# Cart.net
KiCad netlist of a schematic drawn in Altium Designer
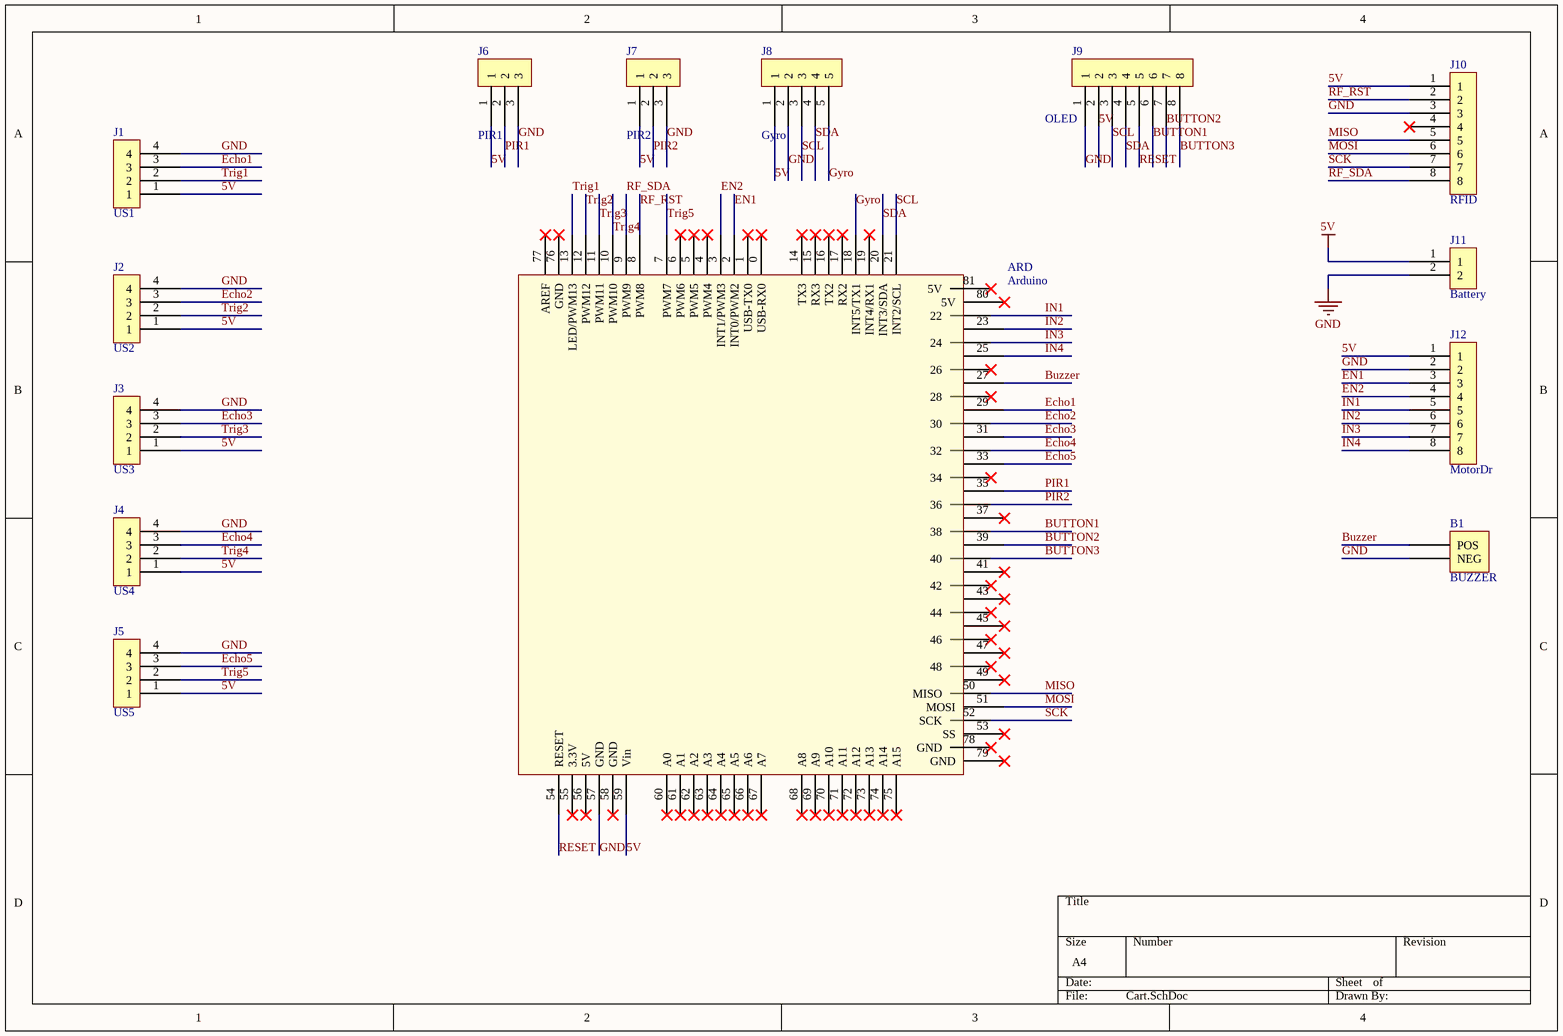
[diagram p0: Cart.SchDoc]

(export (version "E")
  (design (tool "Eeschema 10.0.6"))
  (components
    (comp (ref "ARD")
      (value "Arduino")
      (footprint "Arduino")
      (libsource (lib "Arduino System") (part "Arduino"))
    )
    (comp (ref "B1")
      (value "BUZZER")
      (footprint "new buzzer")
      (description "JST (JAPAN SOLDERLESS TERMINALS) - B8B-XH-A (LF)(SN) - HEADER, VERTICAL, 8WAY")
      (fields
        (field (name "MANUFACTURER") "JST")
        (field (name "MANUFACTURER PART NUMBER") "B8B-XH-A(LF)(SN)")
      )
      (libsource (lib "Schlib1") (part "BUZZER"))
    )
    (comp (ref "J1")
      (value "US1")
      (footprint "JST4")
      (description "JST (JAPAN SOLDERLESS TERMINALS) - B8B-XH-A (LF)(SN) - HEADER, VERTICAL, 8WAY")
      (fields
        (field (name "MANUFACTURER") "JST")
        (field (name "MANUFACTURER PART NUMBER") "B8B-XH-A(LF)(SN)")
      )
      (libsource (lib "Schlib1") (part "JST 4 PIN"))
    )
    (comp (ref "J2")
      (value "US2")
      (footprint "JST4")
      (description "JST (JAPAN SOLDERLESS TERMINALS) - B8B-XH-A (LF)(SN) - HEADER, VERTICAL, 8WAY")
      (fields
        (field (name "MANUFACTURER") "JST")
        (field (name "MANUFACTURER PART NUMBER") "B8B-XH-A(LF)(SN)")
      )
      (libsource (lib "Schlib1") (part "JST 4 PIN"))
    )
    (comp (ref "J3")
      (value "US3")
      (footprint "JST4")
      (description "JST (JAPAN SOLDERLESS TERMINALS) - B8B-XH-A (LF)(SN) - HEADER, VERTICAL, 8WAY")
      (fields
        (field (name "MANUFACTURER") "JST")
        (field (name "MANUFACTURER PART NUMBER") "B8B-XH-A(LF)(SN)")
      )
      (libsource (lib "Schlib1") (part "JST 4 PIN"))
    )
    (comp (ref "J4")
      (value "US4")
      (footprint "JST4")
      (description "JST (JAPAN SOLDERLESS TERMINALS) - B8B-XH-A (LF)(SN) - HEADER, VERTICAL, 8WAY")
      (fields
        (field (name "MANUFACTURER") "JST")
        (field (name "MANUFACTURER PART NUMBER") "B8B-XH-A(LF)(SN)")
      )
      (libsource (lib "Schlib1") (part "JST 4 PIN"))
    )
    (comp (ref "J5")
      (value "US5")
      (footprint "JST4")
      (description "JST (JAPAN SOLDERLESS TERMINALS) - B8B-XH-A (LF)(SN) - HEADER, VERTICAL, 8WAY")
      (fields
        (field (name "MANUFACTURER") "JST")
        (field (name "MANUFACTURER PART NUMBER") "B8B-XH-A(LF)(SN)")
      )
      (libsource (lib "Schlib1") (part "JST 4 PIN"))
    )
    (comp (ref "J6")
      (value "PIR1")
      (footprint "JST3")
      (description "JST (JAPAN SOLDERLESS TERMINALS) - B8B-XH-A (LF)(SN) - HEADER, VERTICAL, 8WAY")
      (fields
        (field (name "MANUFACTURER") "JST")
        (field (name "MANUFACTURER PART NUMBER") "B8B-XH-A(LF)(SN)")
      )
      (libsource (lib "Schlib1") (part "JST 3 PIN"))
    )
    (comp (ref "J7")
      (value "PIR2")
      (footprint "JST3")
      (description "JST (JAPAN SOLDERLESS TERMINALS) - B8B-XH-A (LF)(SN) - HEADER, VERTICAL, 8WAY")
      (fields
        (field (name "MANUFACTURER") "JST")
        (field (name "MANUFACTURER PART NUMBER") "B8B-XH-A(LF)(SN)")
      )
      (libsource (lib "Schlib1") (part "JST 3 PIN"))
    )
    (comp (ref "J8")
      (value "Gyro")
      (footprint "JST5")
      (description "JST (JAPAN SOLDERLESS TERMINALS) - B8B-XH-A (LF)(SN) - HEADER, VERTICAL, 8WAY")
      (fields
        (field (name "MANUFACTURER") "JST")
        (field (name "MANUFACTURER PART NUMBER") "B8B-XH-A(LF)(SN)")
      )
      (libsource (lib "Schlib1") (part "JST 5 PIN"))
    )
    (comp (ref "J9")
      (value "OLED")
      (footprint "JST8")
      (description "JST (JAPAN SOLDERLESS TERMINALS) - B8B-XH-A (LF)(SN) - HEADER, VERTICAL, 8WAY")
      (fields
        (field (name "MANUFACTURER") "JST")
        (field (name "MANUFACTURER PART NUMBER") "B8B-XH-A(LF)(SN)")
      )
      (libsource (lib "") (part "JST 8 PIN_1"))
    )
    (comp (ref "J10")
      (value "RFID")
      (footprint "JST8")
      (description "JST (JAPAN SOLDERLESS TERMINALS) - B8B-XH-A (LF)(SN) - HEADER, VERTICAL, 8WAY")
      (fields
        (field (name "MANUFACTURER") "JST")
        (field (name "MANUFACTURER PART NUMBER") "B8B-XH-A(LF)(SN)")
      )
      (libsource (lib "Schlib1") (part "JST 8 PIN"))
    )
    (comp (ref "J11")
      (value "Battery")
      (footprint "JST2")
      (description "JST (JAPAN SOLDERLESS TERMINALS) - B8B-XH-A (LF)(SN) - HEADER, VERTICAL, 8WAY")
      (fields
        (field (name "MANUFACTURER") "JST")
        (field (name "MANUFACTURER PART NUMBER") "B8B-XH-A(LF)(SN)")
      )
      (libsource (lib "Schlib1") (part "JST 2 PIN"))
    )
    (comp (ref "J12")
      (value "MotorDr")
      (footprint "JST8")
      (description "JST (JAPAN SOLDERLESS TERMINALS) - B8B-XH-A (LF)(SN) - HEADER, VERTICAL, 8WAY")
      (fields
        (field (name "MANUFACTURER") "JST")
        (field (name "MANUFACTURER PART NUMBER") "B8B-XH-A(LF)(SN)")
      )
      (libsource (lib "Schlib1") (part "JST 8 PIN"))
    )
  )
  (nets
    (net (code "1") (name "/BUTTON1") (class "Default")
      (node (ref "ARD") (pin "38") (pinfunction "38_38") (pintype "passive"))
      (node (ref "J9") (pin "6") (pinfunction "6_6") (pintype "passive"))
    )
    (net (code "2") (name "/BUTTON2") (class "Default")
      (node (ref "ARD") (pin "39") (pinfunction "39_39") (pintype "passive"))
      (node (ref "J9") (pin "7") (pinfunction "7_7") (pintype "passive"))
    )
    (net (code "3") (name "/BUTTON3") (class "Default")
      (node (ref "ARD") (pin "40") (pinfunction "40_40") (pintype "passive"))
      (node (ref "J9") (pin "8") (pinfunction "8_8") (pintype "passive"))
    )
    (net (code "4") (name "/Buzzer") (class "Default")
      (node (ref "ARD") (pin "27") (pinfunction "27_27") (pintype "passive"))
      (node (ref "B1") (pin "1") (pinfunction "POS_1") (pintype "passive"))
    )
    (net (code "5") (name "/EN1") (class "Default")
      (node (ref "ARD") (pin "2") (pinfunction "INT0/PWM2_2") (pintype "passive"))
      (node (ref "J12") (pin "3") (pinfunction "3_3") (pintype "passive"))
    )
    (net (code "6") (name "/EN2") (class "Default")
      (node (ref "ARD") (pin "3") (pinfunction "INT1/PWM3_3") (pintype "passive"))
      (node (ref "J12") (pin "4") (pinfunction "4_4") (pintype "passive"))
    )
    (net (code "7") (name "/Echo1") (class "Default")
      (node (ref "ARD") (pin "29") (pinfunction "29_29") (pintype "passive"))
      (node (ref "J1") (pin "3") (pinfunction "3_3") (pintype "passive"))
    )
    (net (code "8") (name "/Echo2") (class "Default")
      (node (ref "ARD") (pin "30") (pinfunction "30_30") (pintype "passive"))
      (node (ref "J2") (pin "3") (pinfunction "3_3") (pintype "passive"))
    )
    (net (code "9") (name "/Echo3") (class "Default")
      (node (ref "ARD") (pin "31") (pinfunction "31_31") (pintype "passive"))
      (node (ref "J3") (pin "3") (pinfunction "3_3") (pintype "passive"))
    )
    (net (code "10") (name "/Echo4") (class "Default")
      (node (ref "ARD") (pin "32") (pinfunction "32_32") (pintype "passive"))
      (node (ref "J4") (pin "3") (pinfunction "3_3") (pintype "passive"))
    )
    (net (code "11") (name "/Echo5") (class "Default")
      (node (ref "ARD") (pin "33") (pinfunction "33_33") (pintype "passive"))
      (node (ref "J5") (pin "3") (pinfunction "3_3") (pintype "passive"))
    )
    (net (code "12") (name "/Gyro") (class "Default")
      (node (ref "ARD") (pin "18") (pinfunction "INT5/TX1_18") (pintype "passive"))
      (node (ref "J8") (pin "5") (pinfunction "5_5") (pintype "passive"))
    )
    (net (code "13") (name "/IN1") (class "Default")
      (node (ref "ARD") (pin "22") (pinfunction "22_22") (pintype "passive"))
      (node (ref "J12") (pin "5") (pinfunction "5_5") (pintype "passive"))
    )
    (net (code "14") (name "/IN2") (class "Default")
      (node (ref "ARD") (pin "23") (pinfunction "23_23") (pintype "passive"))
      (node (ref "J12") (pin "6") (pinfunction "6_6") (pintype "passive"))
    )
    (net (code "15") (name "/IN3") (class "Default")
      (node (ref "ARD") (pin "24") (pinfunction "24_24") (pintype "passive"))
      (node (ref "J12") (pin "7") (pinfunction "7_7") (pintype "passive"))
    )
    (net (code "16") (name "/IN4") (class "Default")
      (node (ref "ARD") (pin "25") (pinfunction "25_25") (pintype "passive"))
      (node (ref "J12") (pin "8") (pinfunction "8_8") (pintype "passive"))
    )
    (net (code "17") (name "/MISO") (class "Default")
      (node (ref "ARD") (pin "50") (pinfunction "MISO_50") (pintype "passive"))
      (node (ref "J10") (pin "5") (pinfunction "5_5") (pintype "passive"))
    )
    (net (code "18") (name "/MOSI") (class "Default")
      (node (ref "ARD") (pin "51") (pinfunction "MOSI_51") (pintype "passive"))
      (node (ref "J10") (pin "6") (pinfunction "6_6") (pintype "passive"))
    )
    (net (code "19") (name "/PIR1") (class "Default")
      (node (ref "ARD") (pin "35") (pinfunction "35_35") (pintype "passive"))
      (node (ref "J6") (pin "2") (pinfunction "2_2") (pintype "passive"))
    )
    (net (code "20") (name "/PIR2") (class "Default")
      (node (ref "ARD") (pin "36") (pinfunction "36_36") (pintype "passive"))
      (node (ref "J7") (pin "2") (pinfunction "2_2") (pintype "passive"))
    )
    (net (code "21") (name "/RESET") (class "Default")
      (node (ref "ARD") (pin "54") (pinfunction "RESET_54") (pintype "passive"))
      (node (ref "J9") (pin "5") (pinfunction "5_5") (pintype "passive"))
    )
    (net (code "22") (name "/RF_RST") (class "Default")
      (node (ref "ARD") (pin "8") (pinfunction "PWM8_8") (pintype "passive"))
      (node (ref "J10") (pin "2") (pinfunction "2_2") (pintype "passive"))
    )
    (net (code "23") (name "/RF_SDA") (class "Default")
      (node (ref "ARD") (pin "9") (pinfunction "PWM9_9") (pintype "passive"))
      (node (ref "J10") (pin "8") (pinfunction "8_8") (pintype "passive"))
    )
    (net (code "24") (name "/SCK") (class "Default")
      (node (ref "ARD") (pin "52") (pinfunction "SCK_52") (pintype "passive"))
      (node (ref "J10") (pin "7") (pinfunction "7_7") (pintype "passive"))
    )
    (net (code "25") (name "/SCL") (class "Default")
      (node (ref "ARD") (pin "21") (pinfunction "INT2/SCL_21") (pintype "passive"))
      (node (ref "J8") (pin "3") (pinfunction "3_3") (pintype "passive"))
      (node (ref "J9") (pin "3") (pinfunction "3_3") (pintype "passive"))
    )
    (net (code "26") (name "/SDA") (class "Default")
      (node (ref "ARD") (pin "20") (pinfunction "INT3/SDA_20") (pintype "passive"))
      (node (ref "J8") (pin "4") (pinfunction "4_4") (pintype "passive"))
      (node (ref "J9") (pin "4") (pinfunction "4_4") (pintype "passive"))
    )
    (net (code "27") (name "/Trig1") (class "Default")
      (node (ref "ARD") (pin "13") (pinfunction "LED/PWM13_13") (pintype "passive"))
      (node (ref "J1") (pin "2") (pinfunction "2_2") (pintype "passive"))
    )
    (net (code "28") (name "/Trig2") (class "Default")
      (node (ref "ARD") (pin "12") (pinfunction "PWM12_12") (pintype "passive"))
      (node (ref "J2") (pin "2") (pinfunction "2_2") (pintype "passive"))
    )
    (net (code "29") (name "/Trig3") (class "Default")
      (node (ref "ARD") (pin "11") (pinfunction "PWM11_11") (pintype "passive"))
      (node (ref "J3") (pin "2") (pinfunction "2_2") (pintype "passive"))
    )
    (net (code "30") (name "/Trig4") (class "Default")
      (node (ref "ARD") (pin "10") (pinfunction "PWM10_10") (pintype "passive"))
      (node (ref "J4") (pin "2") (pinfunction "2_2") (pintype "passive"))
    )
    (net (code "31") (name "/Trig5") (class "Default")
      (node (ref "ARD") (pin "7") (pinfunction "PWM7_7") (pintype "passive"))
      (node (ref "J5") (pin "2") (pinfunction "2_2") (pintype "passive"))
    )
    (net (code "32") (name "5V") (class "Default")
      (node (ref "ARD") (pin "59") (pinfunction "Vin_59") (pintype "passive"))
      (node (ref "J1") (pin "1") (pinfunction "1_1") (pintype "passive"))
      (node (ref "J10") (pin "1") (pinfunction "1_1") (pintype "passive"))
      (node (ref "J11") (pin "1") (pinfunction "1_1") (pintype "passive"))
      (node (ref "J12") (pin "1") (pinfunction "1_1") (pintype "passive"))
      (node (ref "J2") (pin "1") (pinfunction "1_1") (pintype "passive"))
      (node (ref "J3") (pin "1") (pinfunction "1_1") (pintype "passive"))
      (node (ref "J4") (pin "1") (pinfunction "1_1") (pintype "passive"))
      (node (ref "J5") (pin "1") (pinfunction "1_1") (pintype "passive"))
      (node (ref "J6") (pin "1") (pinfunction "1_1") (pintype "passive"))
      (node (ref "J7") (pin "1") (pinfunction "1_1") (pintype "passive"))
      (node (ref "J8") (pin "1") (pinfunction "1_1") (pintype "passive"))
      (node (ref "J9") (pin "2") (pinfunction "2_2") (pintype "passive"))
    )
    (net (code "33") (name "GND") (class "Default")
      (node (ref "ARD") (pin "57") (pinfunction "GND_57") (pintype "passive"))
      (node (ref "B1") (pin "2") (pinfunction "NEG_2") (pintype "passive"))
      (node (ref "J1") (pin "4") (pinfunction "4_4") (pintype "passive"))
      (node (ref "J10") (pin "3") (pinfunction "3_3") (pintype "passive"))
      (node (ref "J11") (pin "2") (pinfunction "2_2") (pintype "passive"))
      (node (ref "J12") (pin "2") (pinfunction "2_2") (pintype "passive"))
      (node (ref "J2") (pin "4") (pinfunction "4_4") (pintype "passive"))
      (node (ref "J3") (pin "4") (pinfunction "4_4") (pintype "passive"))
      (node (ref "J4") (pin "4") (pinfunction "4_4") (pintype "passive"))
      (node (ref "J5") (pin "4") (pinfunction "4_4") (pintype "passive"))
      (node (ref "J6") (pin "3") (pinfunction "3_3") (pintype "passive"))
      (node (ref "J7") (pin "3") (pinfunction "3_3") (pintype "passive"))
      (node (ref "J8") (pin "2") (pinfunction "2_2") (pintype "passive"))
      (node (ref "J9") (pin "1") (pinfunction "1_1") (pintype "passive"))
    )
    (net (code "34") (name "unconnected-(ARD-3.3V-Pad55)") (class "Default")
      (node (ref "ARD") (pin "55") (pinfunction "3.3V_55") (pintype "passive+no_connect"))
    )
    (net (code "35") (name "unconnected-(ARD-5V-Pad56)") (class "Default")
      (node (ref "ARD") (pin "56") (pinfunction "5V_56") (pintype "passive+no_connect"))
    )
    (net (code "36") (name "unconnected-(ARD-5V-Pad80)") (class "Default")
      (node (ref "ARD") (pin "80") (pinfunction "5V_80") (pintype "passive+no_connect"))
    )
    (net (code "37") (name "unconnected-(ARD-5V-Pad81)") (class "Default")
      (node (ref "ARD") (pin "81") (pinfunction "5V_81") (pintype "passive+no_connect"))
    )
    (net (code "38") (name "unconnected-(ARD-A0-Pad60)") (class "Default")
      (node (ref "ARD") (pin "60") (pinfunction "A0_60") (pintype "passive+no_connect"))
    )
    (net (code "39") (name "unconnected-(ARD-A1-Pad61)") (class "Default")
      (node (ref "ARD") (pin "61") (pinfunction "A1_61") (pintype "passive+no_connect"))
    )
    (net (code "40") (name "unconnected-(ARD-A2-Pad62)") (class "Default")
      (node (ref "ARD") (pin "62") (pinfunction "A2_62") (pintype "passive+no_connect"))
    )
    (net (code "41") (name "unconnected-(ARD-A3-Pad63)") (class "Default")
      (node (ref "ARD") (pin "63") (pinfunction "A3_63") (pintype "passive+no_connect"))
    )
    (net (code "42") (name "unconnected-(ARD-A4-Pad64)") (class "Default")
      (node (ref "ARD") (pin "64") (pinfunction "A4_64") (pintype "passive+no_connect"))
    )
    (net (code "43") (name "unconnected-(ARD-A5-Pad65)") (class "Default")
      (node (ref "ARD") (pin "65") (pinfunction "A5_65") (pintype "passive+no_connect"))
    )
    (net (code "44") (name "unconnected-(ARD-A6-Pad66)") (class "Default")
      (node (ref "ARD") (pin "66") (pinfunction "A6_66") (pintype "passive+no_connect"))
    )
    (net (code "45") (name "unconnected-(ARD-A7-Pad67)") (class "Default")
      (node (ref "ARD") (pin "67") (pinfunction "A7_67") (pintype "passive+no_connect"))
    )
    (net (code "46") (name "unconnected-(ARD-A8-Pad68)") (class "Default")
      (node (ref "ARD") (pin "68") (pinfunction "A8_68") (pintype "passive+no_connect"))
    )
    (net (code "47") (name "unconnected-(ARD-A9-Pad69)") (class "Default")
      (node (ref "ARD") (pin "69") (pinfunction "A9_69") (pintype "passive+no_connect"))
    )
    (net (code "48") (name "unconnected-(ARD-A10-Pad70)") (class "Default")
      (node (ref "ARD") (pin "70") (pinfunction "A10_70") (pintype "passive+no_connect"))
    )
    (net (code "49") (name "unconnected-(ARD-A11-Pad71)") (class "Default")
      (node (ref "ARD") (pin "71") (pinfunction "A11_71") (pintype "passive+no_connect"))
    )
    (net (code "50") (name "unconnected-(ARD-A12-Pad72)") (class "Default")
      (node (ref "ARD") (pin "72") (pinfunction "A12_72") (pintype "passive+no_connect"))
    )
    (net (code "51") (name "unconnected-(ARD-A13-Pad73)") (class "Default")
      (node (ref "ARD") (pin "73") (pinfunction "A13_73") (pintype "passive+no_connect"))
    )
    (net (code "52") (name "unconnected-(ARD-A14-Pad74)") (class "Default")
      (node (ref "ARD") (pin "74") (pinfunction "A14_74") (pintype "passive+no_connect"))
    )
    (net (code "53") (name "unconnected-(ARD-A15-Pad75)") (class "Default")
      (node (ref "ARD") (pin "75") (pinfunction "A15_75") (pintype "passive+no_connect"))
    )
    (net (code "54") (name "unconnected-(ARD-AREF-Pad77)") (class "Default")
      (node (ref "ARD") (pin "77") (pinfunction "AREF_77") (pintype "passive+no_connect"))
    )
    (net (code "55") (name "unconnected-(ARD-GND-Pad58)") (class "Default")
      (node (ref "ARD") (pin "58") (pinfunction "GND_58") (pintype "passive+no_connect"))
    )
    (net (code "56") (name "unconnected-(ARD-GND-Pad76)") (class "Default")
      (node (ref "ARD") (pin "76") (pinfunction "GND_76") (pintype "passive+no_connect"))
    )
    (net (code "57") (name "unconnected-(ARD-GND-Pad78)") (class "Default")
      (node (ref "ARD") (pin "78") (pinfunction "GND_78") (pintype "passive+no_connect"))
    )
    (net (code "58") (name "unconnected-(ARD-GND-Pad79)") (class "Default")
      (node (ref "ARD") (pin "79") (pinfunction "GND_79") (pintype "passive+no_connect"))
    )
    (net (code "59") (name "unconnected-(ARD-INT4{slash}RX1-Pad19)") (class "Default")
      (node (ref "ARD") (pin "19") (pinfunction "INT4/RX1_19") (pintype "passive+no_connect"))
    )
    (net (code "60") (name "unconnected-(ARD-PWM4-Pad4)") (class "Default")
      (node (ref "ARD") (pin "4") (pinfunction "PWM4_4") (pintype "passive+no_connect"))
    )
    (net (code "61") (name "unconnected-(ARD-PWM5-Pad5)") (class "Default")
      (node (ref "ARD") (pin "5") (pinfunction "PWM5_5") (pintype "passive+no_connect"))
    )
    (net (code "62") (name "unconnected-(ARD-PWM6-Pad6)") (class "Default")
      (node (ref "ARD") (pin "6") (pinfunction "PWM6_6") (pintype "passive+no_connect"))
    )
    (net (code "63") (name "unconnected-(ARD-Pad26)") (class "Default")
      (node (ref "ARD") (pin "26") (pinfunction "26_26") (pintype "passive+no_connect"))
    )
    (net (code "64") (name "unconnected-(ARD-Pad28)") (class "Default")
      (node (ref "ARD") (pin "28") (pinfunction "28_28") (pintype "passive+no_connect"))
    )
    (net (code "65") (name "unconnected-(ARD-Pad34)") (class "Default")
      (node (ref "ARD") (pin "34") (pinfunction "34_34") (pintype "passive+no_connect"))
    )
    (net (code "66") (name "unconnected-(ARD-Pad37)") (class "Default")
      (node (ref "ARD") (pin "37") (pinfunction "37_37") (pintype "passive+no_connect"))
    )
    (net (code "67") (name "unconnected-(ARD-Pad41)") (class "Default")
      (node (ref "ARD") (pin "41") (pinfunction "41_41") (pintype "passive+no_connect"))
    )
    (net (code "68") (name "unconnected-(ARD-Pad42)") (class "Default")
      (node (ref "ARD") (pin "42") (pinfunction "42_42") (pintype "passive+no_connect"))
    )
    (net (code "69") (name "unconnected-(ARD-Pad43)") (class "Default")
      (node (ref "ARD") (pin "43") (pinfunction "43_43") (pintype "passive+no_connect"))
    )
    (net (code "70") (name "unconnected-(ARD-Pad44)") (class "Default")
      (node (ref "ARD") (pin "44") (pinfunction "44_44") (pintype "passive+no_connect"))
    )
    (net (code "71") (name "unconnected-(ARD-Pad45)") (class "Default")
      (node (ref "ARD") (pin "45") (pinfunction "45_45") (pintype "passive+no_connect"))
    )
    (net (code "72") (name "unconnected-(ARD-Pad46)") (class "Default")
      (node (ref "ARD") (pin "46") (pinfunction "46_46") (pintype "passive+no_connect"))
    )
    (net (code "73") (name "unconnected-(ARD-Pad47)") (class "Default")
      (node (ref "ARD") (pin "47") (pinfunction "47_47") (pintype "passive+no_connect"))
    )
    (net (code "74") (name "unconnected-(ARD-Pad48)") (class "Default")
      (node (ref "ARD") (pin "48") (pinfunction "48_48") (pintype "passive+no_connect"))
    )
    (net (code "75") (name "unconnected-(ARD-Pad49)") (class "Default")
      (node (ref "ARD") (pin "49") (pinfunction "49_49") (pintype "passive+no_connect"))
    )
    (net (code "76") (name "unconnected-(ARD-RX2-Pad17)") (class "Default")
      (node (ref "ARD") (pin "17") (pinfunction "RX2_17") (pintype "passive+no_connect"))
    )
    (net (code "77") (name "unconnected-(ARD-RX3-Pad15)") (class "Default")
      (node (ref "ARD") (pin "15") (pinfunction "RX3_15") (pintype "passive+no_connect"))
    )
    (net (code "78") (name "unconnected-(ARD-SS-Pad53)") (class "Default")
      (node (ref "ARD") (pin "53") (pinfunction "SS_53") (pintype "passive+no_connect"))
    )
    (net (code "79") (name "unconnected-(ARD-TX2-Pad16)") (class "Default")
      (node (ref "ARD") (pin "16") (pinfunction "TX2_16") (pintype "passive+no_connect"))
    )
    (net (code "80") (name "unconnected-(ARD-TX3-Pad14)") (class "Default")
      (node (ref "ARD") (pin "14") (pinfunction "TX3_14") (pintype "passive+no_connect"))
    )
    (net (code "81") (name "unconnected-(ARD-USB-RX0-Pad0)") (class "Default")
      (node (ref "ARD") (pin "0") (pinfunction "USB-RX0_0") (pintype "passive+no_connect"))
    )
    (net (code "82") (name "unconnected-(ARD-USB-TX0-Pad1)") (class "Default")
      (node (ref "ARD") (pin "1") (pinfunction "USB-TX0_1") (pintype "passive+no_connect"))
    )
    (net (code "83") (name "unconnected-(J10-Pad4)") (class "Default")
      (node (ref "J10") (pin "4") (pinfunction "4_4") (pintype "passive+no_connect"))
    )
  )
)
